# sendai_pcba.net
KiCad netlist of a schematic drawn in EAGLE
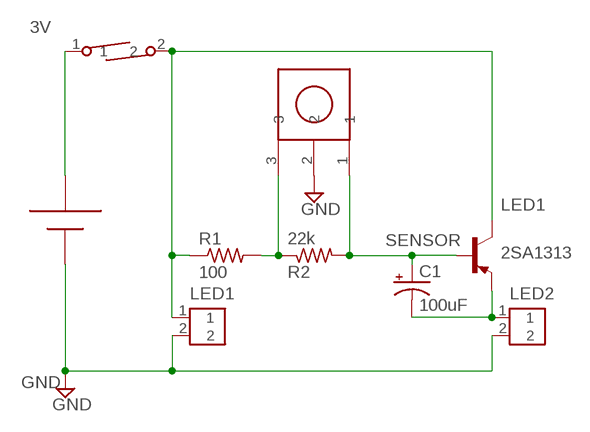
[diagram p0: schematic, sheet 1]

(export (version "E")
  (design (tool "Eeschema 10.0.6"))
  (components
    (comp (ref "C1")
      (value "100uF")
      (footprint "eagle-import:TT2D6")
      (libsource (lib "eagle-import") (part "CPOL-USTT2D6"))
    )
    (comp (ref "R1")
      (value "100")
      (footprint "eagle-import:R0603")
      (libsource (lib "eagle-import") (part "R-US_R0603"))
    )
    (comp (ref "R2")
      (value "22k")
      (footprint "eagle-import:R0603")
      (libsource (lib "eagle-import") (part "R-US_R0603"))
    )
    (comp (ref "T1")
      (value "2SA1313")
      (footprint "eagle-import:SOT23-BEC")
      (libsource (lib "eagle-import") (part "-PNP-SOT23-BEC"))
    )
    (comp (ref "U$1")
      (value "CR2032_VCR2032_V")
      (footprint "eagle-import:CR2032_V")
      (libsource (lib "eagle-import") (part "CR2032_VCR2032_V"))
    )
    (comp (ref "U$2")
      (value "CONNECTER_CON2")
      (footprint "eagle-import:CONNECTER_CON2")
      (libsource (lib "eagle-import") (part "CONNECTER_CON2"))
    )
    (comp (ref "U$3")
      (value "CONNECTER_CON2")
      (footprint "eagle-import:CONNECTER_CON2")
      (libsource (lib "eagle-import") (part "CONNECTER_CON2"))
    )
    (comp (ref "U$4")
      (value "LEAD_SWITCH_LEAD_SWITCH")
      (footprint "eagle-import:LEAD_SWITCH_LEAD_SWITCH")
      (libsource (lib "eagle-import") (part "LEAD_SWITCH_LEAD_SWITCH"))
    )
    (comp (ref "U$5")
      (value "OSRB38C9AA")
      (footprint "eagle-import:OSRB38C9AA")
      (libsource (lib "eagle-import") (part "OSRB38C9AA"))
    )
  )
  (nets
    (net (code "1") (name "/3V") (class "Default")
      (node (ref "U$1") (pin "3") (pinfunction "+_3") (pintype "bidirectional"))
      (node (ref "U$4") (pin "1") (pinfunction "1_1") (pintype "bidirectional"))
    )
    (net (code "2") (name "/LED1") (class "Default")
      (node (ref "R1") (pin "1") (pinfunction "1_1") (pintype "passive"))
      (node (ref "T1") (pin "C") (pinfunction "C_C") (pintype "passive"))
      (node (ref "U$2") (pin "1") (pinfunction "1_1") (pintype "bidirectional"))
      (node (ref "U$4") (pin "2") (pinfunction "2_2") (pintype "bidirectional"))
    )
    (net (code "3") (name "/LED2") (class "Default")
      (node (ref "C1") (pin "-") (pinfunction "-_-") (pintype "passive"))
      (node (ref "T1") (pin "E") (pinfunction "E_E") (pintype "passive"))
      (node (ref "U$3") (pin "1") (pinfunction "1_1") (pintype "bidirectional"))
    )
    (net (code "4") (name "/SENSOR") (class "Default")
      (node (ref "C1") (pin "+") (pinfunction "+_+") (pintype "passive"))
      (node (ref "R2") (pin "2") (pinfunction "2_2") (pintype "passive"))
      (node (ref "T1") (pin "B") (pinfunction "B_B") (pintype "passive"))
      (node (ref "U$5") (pin "1") (pinfunction "1_1") (pintype "bidirectional"))
    )
    (net (code "5") (name "GND") (class "Default")
      (node (ref "U$1") (pin "2") (pinfunction "-_2") (pintype "bidirectional"))
      (node (ref "U$2") (pin "2") (pinfunction "2_2") (pintype "bidirectional"))
      (node (ref "U$3") (pin "2") (pinfunction "2_2") (pintype "bidirectional"))
      (node (ref "U$5") (pin "2") (pinfunction "2_2") (pintype "bidirectional"))
    )
    (net (code "6") (name "Net-(R1-Pad2)") (class "Default")
      (node (ref "R1") (pin "2") (pinfunction "2_2") (pintype "passive"))
      (node (ref "R2") (pin "1") (pinfunction "1_1") (pintype "passive"))
      (node (ref "U$5") (pin "3") (pinfunction "3_3") (pintype "bidirectional"))
    )
  )
)
